# Input.net
KiCad netlist of a schematic drawn in Altium Designer
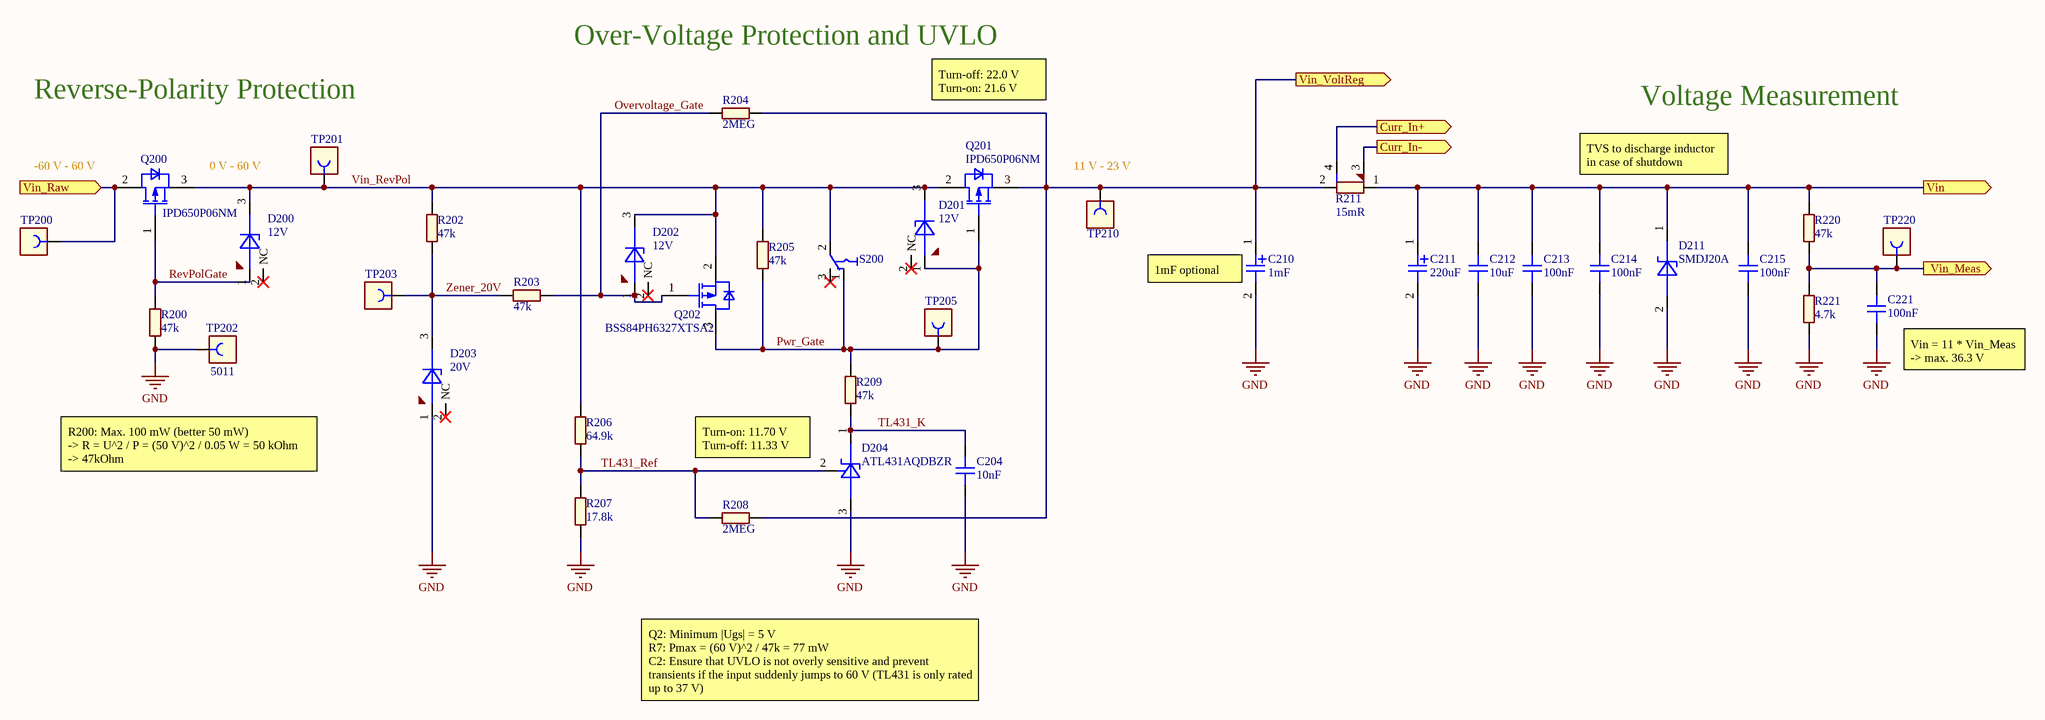
[diagram p0: Input.SchDoc]

(export (version "E")
  (design (tool "Eeschema 10.0.6"))
  (components
    (comp (ref "C204")
      (value "10nF")
      (footprint "CAPC1608X90N-4")
      (description "CAP / CERA / 10nF / 50V / 10% / X8R (EIA) / -55°C to 150°C / 0603(1608) / SMD / -")
      (fields
        (field (name "LEGACY PARTNUMBER") "CAP01010834")
        (field (name "MANUFACTURER") "TDK Corporation")
      )
      (libsource (lib "PCBLibraryData") (part "CAP-SGL-STD-02P_00000001"))
    )
    (comp (ref "C210")
      (value "1mF")
      (footprint "CAPPRD500W60D1300H2700B")
      (fields (field (name "MANUFACTURER") "Kemet"))
      (libsource (lib "PCBLibraryData") (part "CAP-SGL-POL-02P_00000002"))
    )
    (comp (ref "C211")
      (value "220uF")
      (footprint "CAPAE1030X1050N-2")
      (fields (field (name "MANUFACTURER") "Wurth Elektronik"))
      (libsource (lib "PCBLibraryData") (part "CAP-SGL-POL-02P_00000002"))
    )
    (comp (ref "C212")
      (value "10uF")
      (footprint "CAPC3216X190N-1")
      (description "CAP / CERA / 10uF / 50V / 20% / X5R (EIA) / -55°C to 85°C / 1206 (3216) / SMD / -")
      (fields (field (name "MANUFACTURER") "Taiyo Yuden"))
      (libsource (lib "PCBLibraryData") (part "CAP-SGL-STD-02P_00000001"))
    )
    (comp (ref "C213")
      (value "100nF")
      (footprint "CAPC1608X90N-2")
      (description "CAP / CERA / 100nF / 50V / 10% / X7R (EIA) / -55°C to 125°C / 0603 / SMD / -")
      (fields (field (name "MANUFACTURER") "AVX"))
      (libsource (lib "PCBLibraryData") (part "CAP-SGL-STD-02P_00000001"))
    )
    (comp (ref "C214")
      (value "100nF")
      (footprint "CAPC1608X90N-2")
      (description "CAP / CERA / 100nF / 50V / 10% / X7R (EIA) / -55°C to 125°C / 0603 / SMD / -")
      (fields (field (name "MANUFACTURER") "AVX"))
      (libsource (lib "PCBLibraryData") (part "CAP-SGL-STD-02P_00000001"))
    )
    (comp (ref "C215")
      (value "100nF")
      (footprint "CAPC1608X90N-2")
      (description "CAP / CERA / 100nF / 50V / 10% / X7R (EIA) / -55°C to 125°C / 0603 / SMD / -")
      (fields (field (name "MANUFACTURER") "AVX"))
      (libsource (lib "PCBLibraryData") (part "CAP-SGL-STD-02P_00000001"))
    )
    (comp (ref "C221")
      (value "100nF")
      (footprint "CAPC1608X90N-2")
      (description "CAP / CERA / 100nF / 50V / 10% / X7R (EIA) / -55°C to 125°C / 0603 / SMD / -")
      (fields (field (name "MANUFACTURER") "AVX"))
      (libsource (lib "PCBLibraryData") (part "CAP-SGL-STD-02P_00000001"))
    )
    (comp (ref "D200")
      (value "12V")
      (footprint "SOT95P237X111-3N-1")
      (description "Zener Voltage Regulator, 250 mW, 12V")
      (fields (field (name "MANUFACTURER") "ON Semiconductor"))
      (libsource (lib "PCBLibraryData") (part "d_zener_a1c3_3p"))
    )
    (comp (ref "D201")
      (value "12V")
      (footprint "SOT95P237X111-3N-1")
      (description "Zener Voltage Regulator, 250 mW, 12V")
      (fields (field (name "MANUFACTURER") "ON Semiconductor"))
      (libsource (lib "PCBLibraryData") (part "d_zener_a1c3_3p"))
    )
    (comp (ref "D202")
      (value "12V")
      (footprint "SOT95P237X111-3N-1")
      (description "Zener Voltage Regulator, 250 mW, 12V")
      (fields (field (name "MANUFACTURER") "ON Semiconductor"))
      (libsource (lib "PCBLibraryData") (part "d_zener_a1c3_3p"))
    )
    (comp (ref "D203")
      (value "20V")
      (footprint "SOT95P237X111-3N-1")
      (description "Zener Voltage Regulators")
      (fields (field (name "MANUFACTURER") "ON Semiconductor"))
      (libsource (lib "PCBLibraryData") (part "d_zener_a1c3_3p"))
    )
    (comp (ref "D204")
      (value "ATL431AQDBZR")
      (footprint "SOT95P237X112-3N-1")
      (description "ATL431 Adjustable Precision Shunt Regulator")
      (fields (field (name "MANUFACTURER") "Texas Instruments"))
      (libsource (lib "PCBLibraryData") (part "d_tvs_c1a3_3p"))
    )
    (comp (ref "D211")
      (value "SMDJ20A")
      (footprint "DIOM7959X262N")
      (description "TVS Diode, Low Profile Package, Built in Strain Relief, Glass Passivated Chip Junction")
      (fields (field (name "MANUFACTURER") "Littelfuse"))
      (libsource (lib "PCBLibraryData") (part "d_tvs_a"))
    )
    (comp (ref "Q200")
      (value "IPD650P06NM")
      (footprint "TO228P998X250-3N-V2")
      (description "OptiMOS Power Transistor, -60 V")
      (fields (field (name "MANUFACTURER") "Infineon Technologies"))
      (libsource (lib "PCBLibraryData") (part "igfet_p_ch_enh_dio_1g2d3s_3p"))
    )
    (comp (ref "Q201")
      (value "IPD650P06NM")
      (footprint "TO228P998X250-3N-V2")
      (description "OptiMOS Power Transistor, -60 V")
      (fields (field (name "MANUFACTURER") "Infineon Technologies"))
      (libsource (lib "PCBLibraryData") (part "igfet_p_ch_enh_dio_1g2d3s_3p"))
    )
    (comp (ref "Q202")
      (value "BSS84PH6327XTSA2")
      (footprint "SOT95P240X110-3N-1")
      (description "SIPMOS P-Channel Enhancement Small-Signal-Transistor")
      (fields
        (field (name "LEGACY PARTNUMBER") "IFX01400461")
        (field (name "MANUFACTURER") "Infineon Technologies")
      )
      (libsource (lib "PCBLibraryData") (part "igfet_p_ch_enh_dio_1g2s3d_3p"))
    )
    (comp (ref "R200")
      (value "47k")
      (footprint "RESC1609X50N")
      (description "RES / STD / 47k / 100mW / 1% / 100ppm/K / -55°C to 155°C / 0603 / SMD / -")
      (fields (field (name "LEGACY PARTNUMBER") "RES01801333") (field (name "MANUFACTURER") "Vishay"))
      (libsource (lib "PCBLibraryData") (part "RES-SGL-STD-02P_00000006"))
    )
    (comp (ref "R202")
      (value "47k")
      (footprint "RESC1609X50N")
      (description "RES / STD / 47k / 100mW / 1% / 100ppm/K / -55°C to 155°C / 0603 / SMD / -")
      (fields (field (name "LEGACY PARTNUMBER") "RES01801333") (field (name "MANUFACTURER") "Vishay"))
      (libsource (lib "PCBLibraryData") (part "RES-SGL-STD-02P_00000006"))
    )
    (comp (ref "R203")
      (value "47k")
      (footprint "RESC1609X50N")
      (description "RES / STD / 47k / 100mW / 1% / 100ppm/K / -55°C to 155°C / 0603 / SMD / -")
      (fields (field (name "LEGACY PARTNUMBER") "RES01801333") (field (name "MANUFACTURER") "Vishay"))
      (libsource (lib "") (part "RES-SGL-STD-02P_00000006_3"))
    )
    (comp (ref "R204")
      (value "2MEG")
      (footprint "RESC1609X50N")
      (description "RES / STD / 2MEG / 100mW / 1% / 100ppm/K / -55°C to 155°C / 0603 / SMD / -")
      (fields (field (name "LEGACY PARTNUMBER") "RES01801517") (field (name "MANUFACTURER") "Vishay"))
      (libsource (lib "") (part "RES-SGL-STD-02P_00000006_1"))
    )
    (comp (ref "R205")
      (value "47k")
      (footprint "RESC1609X50N")
      (description "RES / STD / 47k / 100mW / 1% / 100ppm/K / -55°C to 155°C / 0603 / SMD / -")
      (fields (field (name "LEGACY PARTNUMBER") "RES01801333") (field (name "MANUFACTURER") "Vishay"))
      (libsource (lib "PCBLibraryData") (part "RES-SGL-STD-02P_00000006"))
    )
    (comp (ref "R206")
      (value "64.9k")
      (footprint "RESC1609X50N")
      (description "RES / STD / 64.9k / 100mW / 1% / 100ppm/K / -55°C to 155°C / 0603 / SMD / -")
      (fields (field (name "LEGACY PARTNUMBER") "RES01801350") (field (name "MANUFACTURER") "Vishay"))
      (libsource (lib "PCBLibraryData") (part "RES-SGL-STD-02P_00000006"))
    )
    (comp (ref "R207")
      (value "17.8k")
      (footprint "RESC1609X50N")
      (description "RES / STD / 17.8k / 100mW / 1% / 100ppm/K / -55°C to 155°C / 0603 / SMD / -")
      (fields (field (name "LEGACY PARTNUMBER") "RES01801283") (field (name "MANUFACTURER") "Vishay"))
      (libsource (lib "PCBLibraryData") (part "RES-SGL-STD-02P_00000006"))
    )
    (comp (ref "R208")
      (value "2MEG")
      (footprint "RESC1609X50N")
      (description "RES / STD / 2MEG / 100mW / 1% / 100ppm/K / -55°C to 155°C / 0603 / SMD / -")
      (fields (field (name "LEGACY PARTNUMBER") "RES01801517") (field (name "MANUFACTURER") "Vishay"))
      (libsource (lib "") (part "RES-SGL-STD-02P_00000006_1"))
    )
    (comp (ref "R209")
      (value "47k")
      (footprint "RESC1609X50N")
      (description "RES / STD / 47k / 100mW / 1% / 100ppm/K / -55°C to 155°C / 0603 / SMD / -")
      (fields (field (name "LEGACY PARTNUMBER") "RES01801333") (field (name "MANUFACTURER") "Vishay"))
      (libsource (lib "PCBLibraryData") (part "RES-SGL-STD-02P_00000006"))
    )
    (comp (ref "R211")
      (value "15mR")
      (footprint "RES-SMD-L4T12")
      (description "RES / STD / 15mR / 500mW / 1% / 75ppm/K / -55°C to 155°C / 1206 (3216) / SMD / -")
      (fields (field (name "MANUFACTURER") "Ohmite"))
      (libsource (lib "PCBLibraryData") (part "RES-SHT-STD-04P_00097BE5"))
    )
    (comp (ref "R220")
      (value "47k")
      (footprint "RESC1609X50N")
      (description "RES / STD / 47k / 100mW / 1% / 100ppm/K / -55°C to 155°C / 0603 / SMD / -")
      (fields (field (name "LEGACY PARTNUMBER") "RES01801333") (field (name "MANUFACTURER") "Vishay"))
      (libsource (lib "") (part "RES-SGL-STD-02P_00000006_2"))
    )
    (comp (ref "R221")
      (value "4.7k")
      (footprint "RESC1609X50N")
      (description "RES / STD / 4.7k / 100mW / 1% / 100ppm/K / -55°C to 155°C / 0603 / SMD / -")
      (fields (field (name "LEGACY PARTNUMBER") "RES01801219") (field (name "MANUFACTURER") "Vishay"))
      (libsource (lib "PCBLibraryData") (part "RES-SGL-STD-02P_00000006"))
    )
    (comp (ref "S200")
      (value "CL-SB-12A-01T")
      (footprint "SW-SMD-CL-SB-12A-01T")
      (description "Slid Switch, 12V, 200mA")
      (fields (field (name "MANUFACTURER") "NIDEC COPAL ELECTRONICS, Inc."))
      (libsource (lib "PCBLibraryData") (part "sw_co213_3p"))
    )
    (comp (ref "TP200")
      (value "S1751-46R")
      (footprint "CON-SMD-TT-S1751-46")
      (description "Test Terminal, Surface Mount (Tape and Reeled Components)")
      (fields (field (name "LEGACY PARTNUMBER") "CON01501015") (field (name "MANUFACTURER") "Harwin"))
      (libsource (lib "") (part "connector_1_f_2"))
    )
    (comp (ref "TP201")
      (value "S1751-46R")
      (footprint "CON-SMD-TT-S1751-46")
      (description "Test Terminal, Surface Mount (Tape and Reeled Components)")
      (fields (field (name "LEGACY PARTNUMBER") "CON01501015") (field (name "MANUFACTURER") "Harwin"))
      (libsource (lib "") (part "connector_1_f_3"))
    )
    (comp (ref "TP202")
      (value "5011")
      (footprint "CON-THT-TP-5011")
      (description "PC Test Point-Multipurpose THT, Black")
      (fields
        (field (name "LEGACY PARTNUMBER") "CON01500530")
        (field (name "MANUFACTURER") "Keystone Electronics Corp.")
      )
      (libsource (lib "PCBLibraryData") (part "connector_1_f"))
    )
    (comp (ref "TP203")
      (value "S1751-46R")
      (footprint "CON-SMD-TT-S1751-46")
      (description "Test Terminal, Surface Mount (Tape and Reeled Components)")
      (fields (field (name "LEGACY PARTNUMBER") "CON01501015") (field (name "MANUFACTURER") "Harwin"))
      (libsource (lib "") (part "connector_1_f_2"))
    )
    (comp (ref "TP205")
      (value "S1751-46R")
      (footprint "CON-SMD-TT-S1751-46")
      (description "Test Terminal, Surface Mount (Tape and Reeled Components)")
      (fields (field (name "LEGACY PARTNUMBER") "CON01501015") (field (name "MANUFACTURER") "Harwin"))
      (libsource (lib "") (part "connector_1_f_3"))
    )
    (comp (ref "TP210")
      (value "S1751-46R")
      (footprint "CON-SMD-TT-S1751-46")
      (description "Test Terminal, Surface Mount (Tape and Reeled Components)")
      (fields (field (name "LEGACY PARTNUMBER") "CON01501015") (field (name "MANUFACTURER") "Harwin"))
      (libsource (lib "") (part "connector_1_f_1"))
    )
    (comp (ref "TP220")
      (value "S1751-46R")
      (footprint "CON-SMD-TT-S1751-46")
      (description "Test Terminal, Surface Mount (Tape and Reeled Components)")
      (fields (field (name "LEGACY PARTNUMBER") "CON01501015") (field (name "MANUFACTURER") "Harwin"))
      (libsource (lib "") (part "connector_1_f_3"))
    )
  )
  (nets
    (net (code "1") (name "/Curr_In+") (class "Default")
      (node (ref "R211") (pin "4") (pinfunction "I2_4") (pintype "passive"))
    )
    (net (code "2") (name "/Curr_In-") (class "Default")
      (node (ref "R211") (pin "3") (pinfunction "I1_3") (pintype "passive"))
    )
    (net (code "3") (name "/Overvoltage_Gate") (class "Default")
      (node (ref "D202") (pin "1") (pinfunction "ANODE_1") (pintype "passive"))
      (node (ref "Q202") (pin "1") (pinfunction "GATE_1") (pintype "passive"))
      (node (ref "R203") (pin "1") (pinfunction "1_1") (pintype "passive"))
      (node (ref "R204") (pin "1") (pinfunction "1_1") (pintype "passive"))
    )
    (net (code "4") (name "/Pwr_Gate") (class "Default")
      (node (ref "D201") (pin "1") (pinfunction "ANODE_1") (pintype "passive"))
      (node (ref "Q201") (pin "1") (pinfunction "GATE_1") (pintype "passive"))
      (node (ref "Q202") (pin "3") (pinfunction "DRAIN_3") (pintype "passive"))
      (node (ref "R205") (pin "1") (pinfunction "1_1") (pintype "passive"))
      (node (ref "R209") (pin "2") (pinfunction "2_2") (pintype "passive"))
      (node (ref "S200") (pin "1") (pinfunction "1_1") (pintype "passive"))
      (node (ref "TP205") (pin "1") (pinfunction "1_1") (pintype "passive"))
    )
    (net (code "5") (name "/RevPolGate") (class "Default")
      (node (ref "D200") (pin "1") (pinfunction "ANODE_1") (pintype "passive"))
      (node (ref "Q200") (pin "1") (pinfunction "GATE_1") (pintype "passive"))
      (node (ref "R200") (pin "2") (pinfunction "2_2") (pintype "passive"))
    )
    (net (code "6") (name "/TL431_K") (class "Default")
      (node (ref "C204") (pin "2") (pinfunction "2_2") (pintype "passive"))
      (node (ref "D204") (pin "1") (pinfunction "CATHODE_1") (pintype "passive"))
      (node (ref "R209") (pin "1") (pinfunction "1_1") (pintype "passive"))
    )
    (net (code "7") (name "/TL431_Ref") (class "Default")
      (node (ref "D204") (pin "2") (pinfunction "REF_2") (pintype "passive"))
      (node (ref "R206") (pin "1") (pinfunction "1_1") (pintype "passive"))
      (node (ref "R207") (pin "2") (pinfunction "2_2") (pintype "passive"))
      (node (ref "R208") (pin "1") (pinfunction "1_1") (pintype "passive"))
    )
    (net (code "8") (name "/Vin") (class "Default")
      (node (ref "C211") (pin "1") (pinfunction "1_1") (pintype "passive"))
      (node (ref "C212") (pin "2") (pinfunction "2_2") (pintype "passive"))
      (node (ref "C213") (pin "2") (pinfunction "2_2") (pintype "passive"))
      (node (ref "C214") (pin "2") (pinfunction "2_2") (pintype "passive"))
      (node (ref "C215") (pin "2") (pinfunction "2_2") (pintype "passive"))
      (node (ref "D211") (pin "1") (pinfunction "CATHODE_1") (pintype "passive"))
      (node (ref "R211") (pin "1") (pinfunction "V1_1") (pintype "passive"))
      (node (ref "R220") (pin "1") (pinfunction "1_1") (pintype "passive"))
    )
    (net (code "9") (name "/Vin_Meas") (class "Default")
      (node (ref "C221") (pin "2") (pinfunction "2_2") (pintype "passive"))
      (node (ref "R220") (pin "2") (pinfunction "2_2") (pintype "passive"))
      (node (ref "R221") (pin "2") (pinfunction "2_2") (pintype "passive"))
      (node (ref "TP220") (pin "1") (pinfunction "1_1") (pintype "passive"))
    )
    (net (code "10") (name "/Vin_Raw") (class "Default")
      (node (ref "Q200") (pin "2") (pinfunction "DRAIN_2") (pintype "passive"))
      (node (ref "TP200") (pin "1") (pinfunction "1_1") (pintype "passive"))
    )
    (net (code "11") (name "/Vin_RevPol") (class "Default")
      (node (ref "D200") (pin "3") (pinfunction "CATHODE_3") (pintype "passive"))
      (node (ref "D201") (pin "3") (pinfunction "CATHODE_3") (pintype "passive"))
      (node (ref "D202") (pin "3") (pinfunction "CATHODE_3") (pintype "passive"))
      (node (ref "Q200") (pin "3") (pinfunction "SOURCE_3") (pintype "passive"))
      (node (ref "Q201") (pin "2") (pinfunction "DRAIN_2") (pintype "passive"))
      (node (ref "Q202") (pin "2") (pinfunction "SOURCE_2") (pintype "passive"))
      (node (ref "R202") (pin "2") (pinfunction "2_2") (pintype "passive"))
      (node (ref "R205") (pin "2") (pinfunction "2_2") (pintype "passive"))
      (node (ref "R206") (pin "2") (pinfunction "2_2") (pintype "passive"))
      (node (ref "S200") (pin "2") (pinfunction "2_2") (pintype "passive"))
      (node (ref "TP201") (pin "1") (pinfunction "1_1") (pintype "passive"))
    )
    (net (code "12") (name "/Vin_VoltReg") (class "Default")
      (node (ref "C210") (pin "1") (pinfunction "1_1") (pintype "passive"))
      (node (ref "Q201") (pin "3") (pinfunction "SOURCE_3") (pintype "passive"))
      (node (ref "R204") (pin "2") (pinfunction "2_2") (pintype "passive"))
      (node (ref "R208") (pin "2") (pinfunction "2_2") (pintype "passive"))
      (node (ref "R211") (pin "2") (pinfunction "V2_2") (pintype "passive"))
      (node (ref "TP210") (pin "1") (pinfunction "1_1") (pintype "passive"))
    )
    (net (code "13") (name "/Zener_20V") (class "Default")
      (node (ref "D203") (pin "3") (pinfunction "CATHODE_3") (pintype "passive"))
      (node (ref "R202") (pin "1") (pinfunction "1_1") (pintype "passive"))
      (node (ref "R203") (pin "2") (pinfunction "2_2") (pintype "passive"))
      (node (ref "TP203") (pin "1") (pinfunction "1_1") (pintype "passive"))
    )
    (net (code "14") (name "GND") (class "Default")
      (node (ref "C204") (pin "1") (pinfunction "1_1") (pintype "passive"))
      (node (ref "C210") (pin "2") (pinfunction "2_2") (pintype "passive"))
      (node (ref "C211") (pin "2") (pinfunction "2_2") (pintype "passive"))
      (node (ref "C212") (pin "1") (pinfunction "1_1") (pintype "passive"))
      (node (ref "C213") (pin "1") (pinfunction "1_1") (pintype "passive"))
      (node (ref "C214") (pin "1") (pinfunction "1_1") (pintype "passive"))
      (node (ref "C215") (pin "1") (pinfunction "1_1") (pintype "passive"))
      (node (ref "C221") (pin "1") (pinfunction "1_1") (pintype "passive"))
      (node (ref "D203") (pin "1") (pinfunction "ANODE_1") (pintype "passive"))
      (node (ref "D204") (pin "3") (pinfunction "ANODE_3") (pintype "passive"))
      (node (ref "D211") (pin "2") (pinfunction "ANODE_2") (pintype "passive"))
      (node (ref "R200") (pin "1") (pinfunction "1_1") (pintype "passive"))
      (node (ref "R207") (pin "1") (pinfunction "1_1") (pintype "passive"))
      (node (ref "R221") (pin "1") (pinfunction "1_1") (pintype "passive"))
      (node (ref "TP202") (pin "1") (pinfunction "1_1") (pintype "passive"))
    )
    (net (code "15") (name "unconnected-(D200-NC-Pad2)") (class "Default")
      (node (ref "D200") (pin "2") (pinfunction "NC_2") (pintype "passive+no_connect"))
    )
    (net (code "16") (name "unconnected-(D201-NC-Pad2)") (class "Default")
      (node (ref "D201") (pin "2") (pinfunction "NC_2") (pintype "passive+no_connect"))
    )
    (net (code "17") (name "unconnected-(D202-NC-Pad2)") (class "Default")
      (node (ref "D202") (pin "2") (pinfunction "NC_2") (pintype "passive+no_connect"))
    )
    (net (code "18") (name "unconnected-(D203-NC-Pad2)") (class "Default")
      (node (ref "D203") (pin "2") (pinfunction "NC_2") (pintype "passive+no_connect"))
    )
    (net (code "19") (name "unconnected-(S200-Pad3)") (class "Default")
      (node (ref "S200") (pin "3") (pinfunction "3_3") (pintype "passive+no_connect"))
    )
  )
)
